# 05_ZYNQ_ETHERNET.net
KiCad netlist of a schematic drawn in Altium Designer
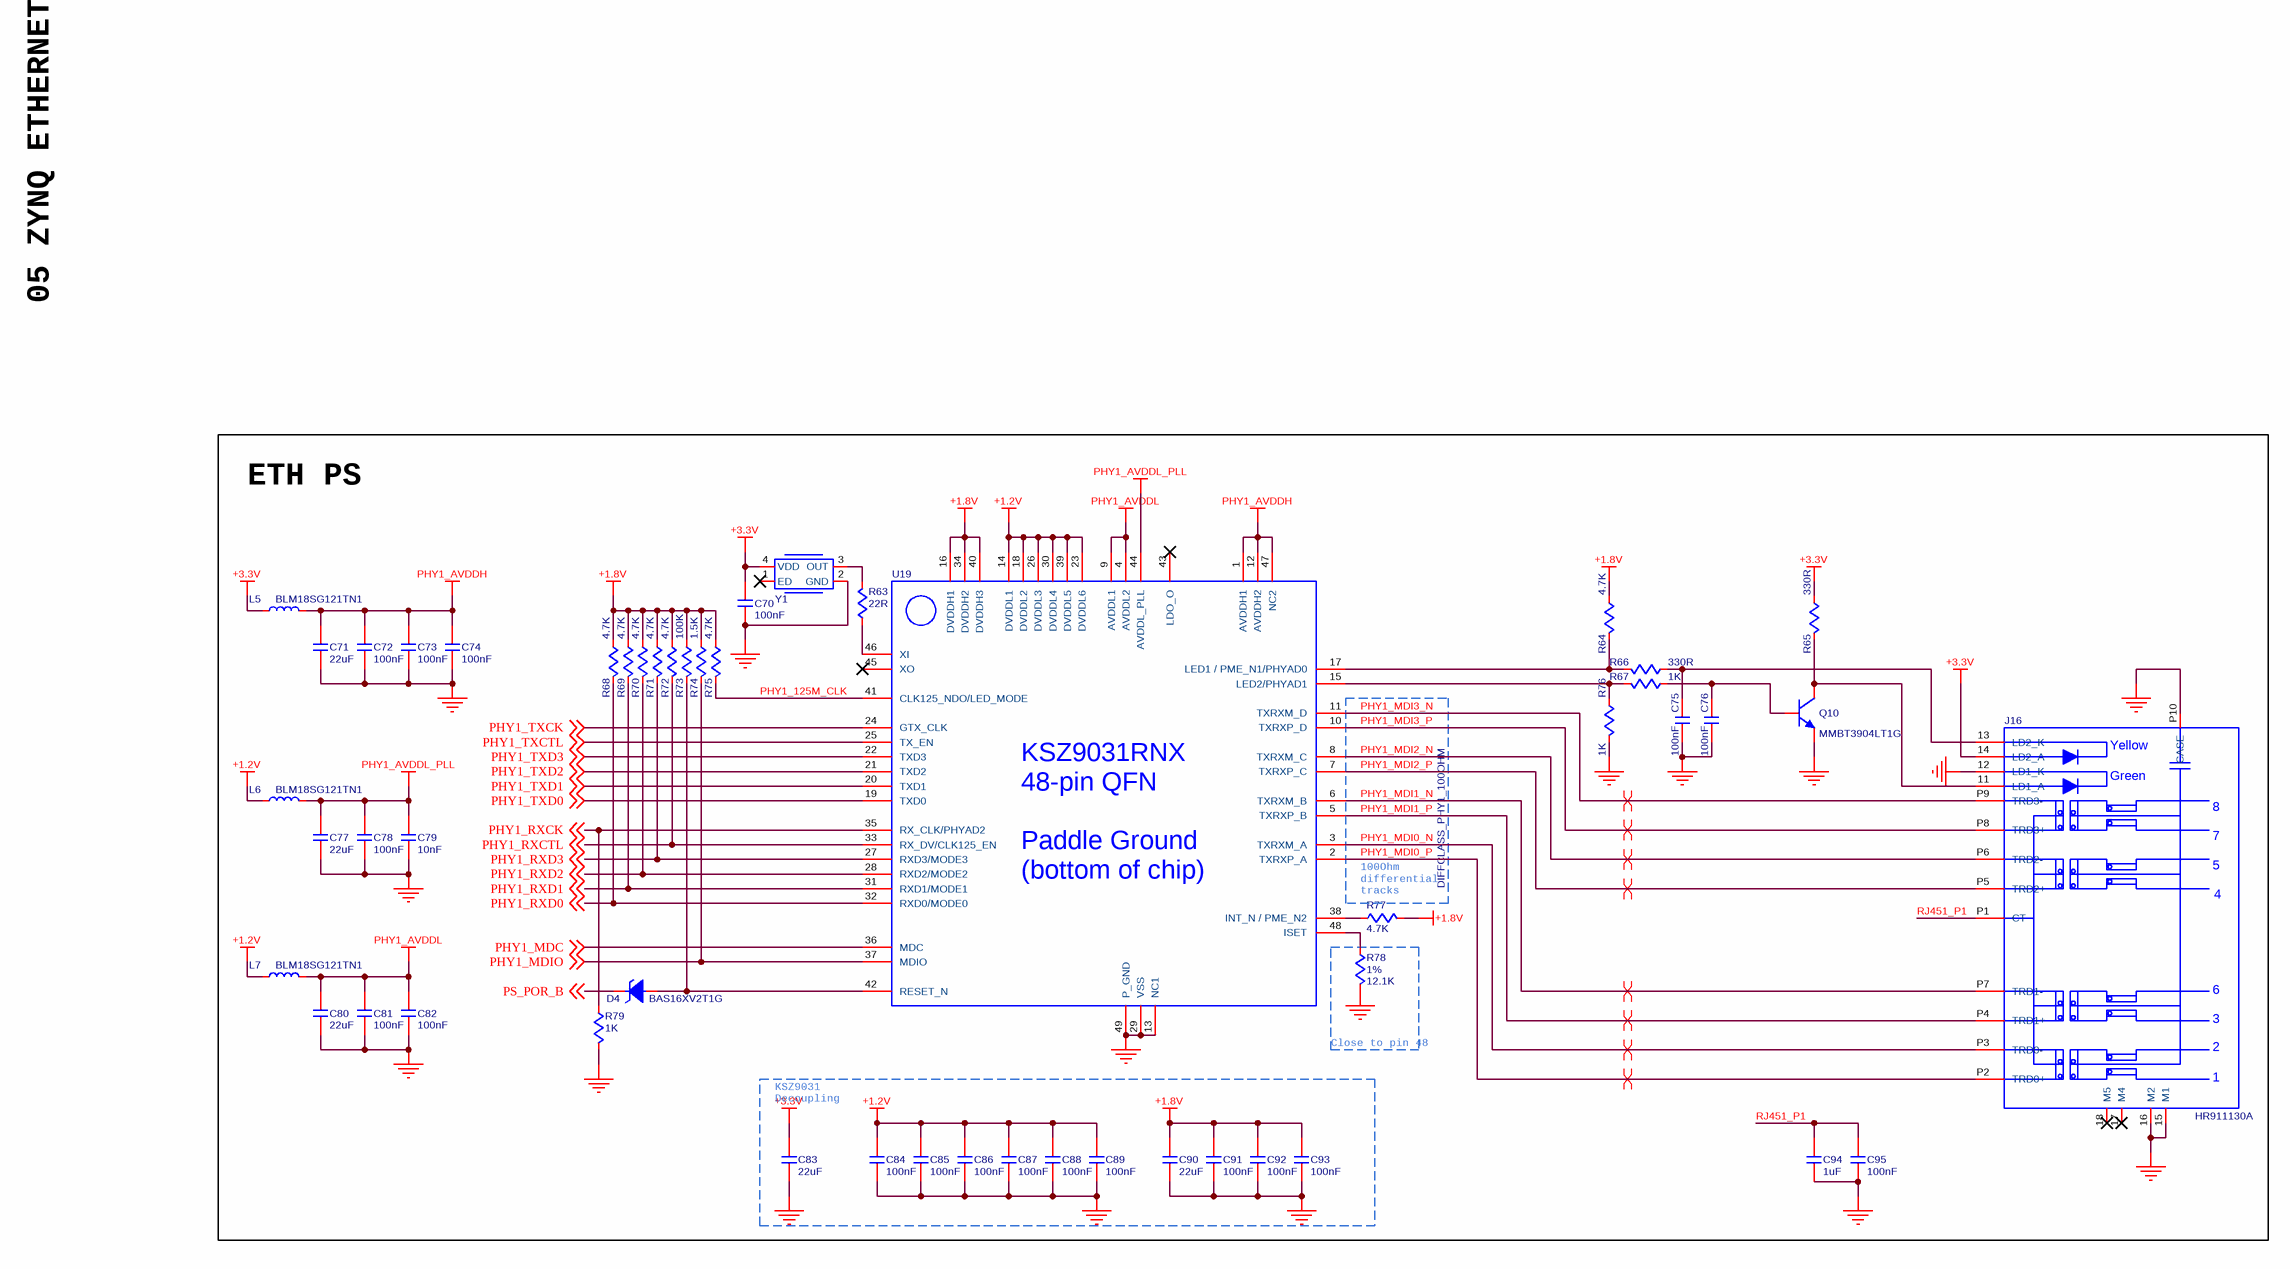
[diagram p0: 05_ZYNQ_ETHERNET.SchDoc]

(export (version "E")
  (design (tool "Eeschema 10.0.6"))
  (components
    (comp (ref "C70")
      (value "100nF")
      (footprint "zynq:C0402")
      (fields (field (name "VOLTAGE") "25V") (field (name "Comment") "C-NOMO"))
      (libsource (lib "zynq") (part "C-NOMO"))
    )
    (comp (ref "C71")
      (value "22uF")
      (footprint "zynq:C0805")
      (fields (field (name "VOLTAGE") "25V") (field (name "Comment") "C-NOMO"))
      (libsource (lib "zynq") (part "C-NOMO"))
    )
    (comp (ref "C72")
      (value "100nF")
      (footprint "zynq:C0402")
      (fields (field (name "VOLTAGE") "25V") (field (name "Comment") "C-NOMO"))
      (libsource (lib "zynq") (part "C-NOMO"))
    )
    (comp (ref "C73")
      (value "100nF")
      (footprint "zynq:C0402")
      (fields (field (name "VOLTAGE") "25V") (field (name "Comment") "C-NOMO"))
      (libsource (lib "zynq") (part "C-NOMO"))
    )
    (comp (ref "C74")
      (value "100nF")
      (footprint "zynq:C0402")
      (fields (field (name "VOLTAGE") "25V") (field (name "Comment") "C-NOMO"))
      (libsource (lib "zynq") (part "C-NOMO"))
    )
    (comp (ref "C75")
      (value "100nF")
      (footprint "zynq:C0402")
      (fields (field (name "VOLTAGE") "25V") (field (name "Comment") "C-NOMO"))
      (libsource (lib "zynq") (part "C-NOMO"))
    )
    (comp (ref "C76")
      (value "100nF")
      (footprint "zynq:C0402")
      (fields (field (name "VOLTAGE") "25V") (field (name "Comment") "C-NOMO"))
      (libsource (lib "zynq") (part "C-NOMO"))
    )
    (comp (ref "C77")
      (value "22uF")
      (footprint "zynq:C0805")
      (fields (field (name "VOLTAGE") "25V") (field (name "Comment") "C-NOMO"))
      (libsource (lib "zynq") (part "C-NOMO"))
    )
    (comp (ref "C78")
      (value "100nF")
      (footprint "zynq:C0402")
      (fields (field (name "VOLTAGE") "25V") (field (name "Comment") "C-NOMO"))
      (libsource (lib "zynq") (part "C-NOMO"))
    )
    (comp (ref "C79")
      (value "10nF")
      (footprint "zynq:C0402")
      (fields (field (name "VOLTAGE") "25V") (field (name "Comment") "C-NOMO"))
      (libsource (lib "zynq") (part "C-NOMO"))
    )
    (comp (ref "C80")
      (value "22uF")
      (footprint "zynq:C0805")
      (fields (field (name "VOLTAGE") "25V") (field (name "Comment") "C-NOMO"))
      (libsource (lib "zynq") (part "C-NOMO"))
    )
    (comp (ref "C81")
      (value "100nF")
      (footprint "zynq:C0402")
      (fields (field (name "VOLTAGE") "25V") (field (name "Comment") "C-NOMO"))
      (libsource (lib "zynq") (part "C-NOMO"))
    )
    (comp (ref "C82")
      (value "100nF")
      (footprint "zynq:C0402")
      (fields (field (name "VOLTAGE") "25V") (field (name "Comment") "C-NOMO"))
      (libsource (lib "zynq") (part "C-NOMO"))
    )
    (comp (ref "C83")
      (value "22uF")
      (footprint "zynq:C0805")
      (fields (field (name "VOLTAGE") "25V") (field (name "Comment") "C-NOMO"))
      (libsource (lib "zynq") (part "C-NOMO"))
    )
    (comp (ref "C84")
      (value "100nF")
      (footprint "zynq:C0402")
      (fields (field (name "VOLTAGE") "25V") (field (name "Comment") "C-NOMO"))
      (libsource (lib "zynq") (part "C-NOMO"))
    )
    (comp (ref "C85")
      (value "100nF")
      (footprint "zynq:C0402")
      (fields (field (name "VOLTAGE") "25V") (field (name "Comment") "C-NOMO"))
      (libsource (lib "zynq") (part "C-NOMO"))
    )
    (comp (ref "C86")
      (value "100nF")
      (footprint "zynq:C0402")
      (fields (field (name "VOLTAGE") "25V") (field (name "Comment") "C-NOMO"))
      (libsource (lib "zynq") (part "C-NOMO"))
    )
    (comp (ref "C87")
      (value "100nF")
      (footprint "zynq:C0402")
      (fields (field (name "VOLTAGE") "25V") (field (name "Comment") "C-NOMO"))
      (libsource (lib "zynq") (part "C-NOMO"))
    )
    (comp (ref "C88")
      (value "100nF")
      (footprint "zynq:C0402")
      (fields (field (name "VOLTAGE") "25V") (field (name "Comment") "C-NOMO"))
      (libsource (lib "zynq") (part "C-NOMO"))
    )
    (comp (ref "C89")
      (value "100nF")
      (footprint "zynq:C0402")
      (fields (field (name "VOLTAGE") "25V") (field (name "Comment") "C-NOMO"))
      (libsource (lib "zynq") (part "C-NOMO"))
    )
    (comp (ref "C90")
      (value "22uF")
      (footprint "zynq:C0805")
      (fields (field (name "VOLTAGE") "25V") (field (name "Comment") "C-NOMO"))
      (libsource (lib "zynq") (part "C-NOMO"))
    )
    (comp (ref "C91")
      (value "100nF")
      (footprint "zynq:C0402")
      (fields (field (name "VOLTAGE") "25V") (field (name "Comment") "C-NOMO"))
      (libsource (lib "zynq") (part "C-NOMO"))
    )
    (comp (ref "C92")
      (value "100nF")
      (footprint "zynq:C0402")
      (fields (field (name "VOLTAGE") "25V") (field (name "Comment") "C-NOMO"))
      (libsource (lib "zynq") (part "C-NOMO"))
    )
    (comp (ref "C93")
      (value "100nF")
      (footprint "zynq:C0402")
      (fields (field (name "VOLTAGE") "25V") (field (name "Comment") "C-NOMO"))
      (libsource (lib "zynq") (part "C-NOMO"))
    )
    (comp (ref "C94")
      (value "1uF")
      (footprint "zynq:C0402")
      (fields (field (name "VOLTAGE") "25V") (field (name "Comment") "C-NOMO"))
      (libsource (lib "zynq") (part "C-NOMO"))
    )
    (comp (ref "C95")
      (value "100nF")
      (footprint "zynq:C0402")
      (fields (field (name "VOLTAGE") "25V") (field (name "Comment") "C-NOMO"))
      (libsource (lib "zynq") (part "C-NOMO"))
    )
    (comp (ref "D4") (value "BAS16XV2T1G") (footprint "zynq:SOD-523") (libsource (lib "zynq") (part "DIOD2")))
    (comp (ref "J16")
      (value "HR911130A")
      (footprint "zynq:RJ45-GE")
      (libsource (lib "zynq") (part "RJ45-GE"))
    )
    (comp (ref "L5")
      (value "BLM18SG121TN1")
      (footprint "zynq:L0603")
      (fields (field (name "PUBLISHER") "Altium Limited"))
      (libsource (lib "zynq") (part "L"))
    )
    (comp (ref "L6")
      (value "BLM18SG121TN1")
      (footprint "zynq:L0603")
      (fields (field (name "PUBLISHER") "Altium Limited"))
      (libsource (lib "zynq") (part "L"))
    )
    (comp (ref "L7")
      (value "BLM18SG121TN1")
      (footprint "zynq:L0603")
      (fields (field (name "PUBLISHER") "Altium Limited"))
      (libsource (lib "zynq") (part "L"))
    )
    (comp (ref "Q10") (value "MMBT3904LT1G") (footprint "zynq:SOT-23") (libsource (lib "zynq") (part "NPN")))
    (comp (ref "R63")
      (value "22R")
      (footprint "zynq:R0402")
      (fields (field (name "Comment") "R"))
      (libsource (lib "zynq") (part "R"))
    )
    (comp (ref "R64")
      (value "4.7K")
      (footprint "zynq:R0402")
      (fields (field (name "Comment") "R"))
      (libsource (lib "zynq") (part "R"))
    )
    (comp (ref "R65")
      (value "330R")
      (footprint "zynq:R0402")
      (fields (field (name "Comment") "R"))
      (libsource (lib "zynq") (part "R"))
    )
    (comp (ref "R66")
      (value "330R")
      (footprint "zynq:R0402")
      (fields (field (name "Comment") "R"))
      (libsource (lib "zynq") (part "R"))
    )
    (comp (ref "R67")
      (value "1K")
      (footprint "zynq:R0402")
      (fields (field (name "Comment") "R"))
      (libsource (lib "zynq") (part "R"))
    )
    (comp (ref "R68")
      (value "4.7K")
      (footprint "zynq:R0402")
      (fields (field (name "Comment") "R"))
      (libsource (lib "zynq") (part "R"))
    )
    (comp (ref "R69")
      (value "4.7K")
      (footprint "zynq:R0402")
      (fields (field (name "Comment") "R"))
      (libsource (lib "zynq") (part "R"))
    )
    (comp (ref "R70")
      (value "4.7K")
      (footprint "zynq:R0402")
      (fields (field (name "Comment") "R"))
      (libsource (lib "zynq") (part "R"))
    )
    (comp (ref "R71")
      (value "4.7K")
      (footprint "zynq:R0402")
      (fields (field (name "Comment") "R"))
      (libsource (lib "zynq") (part "R"))
    )
    (comp (ref "R72")
      (value "4.7K")
      (footprint "zynq:R0402")
      (fields (field (name "Comment") "R"))
      (libsource (lib "zynq") (part "R"))
    )
    (comp (ref "R73")
      (value "100K")
      (footprint "zynq:R0402")
      (fields (field (name "Comment") "R"))
      (libsource (lib "zynq") (part "R"))
    )
    (comp (ref "R74")
      (value "1.5K")
      (footprint "zynq:R0402")
      (fields (field (name "Comment") "R"))
      (libsource (lib "zynq") (part "R"))
    )
    (comp (ref "R75")
      (value "4.7K")
      (footprint "zynq:R0402")
      (fields (field (name "Comment") "R"))
      (libsource (lib "zynq") (part "R"))
    )
    (comp (ref "R76")
      (value "1K")
      (footprint "zynq:R0402")
      (fields (field (name "Comment") "R"))
      (libsource (lib "zynq") (part "R"))
    )
    (comp (ref "R77")
      (value "4.7K")
      (footprint "zynq:R0402")
      (fields (field (name "Comment") "R"))
      (libsource (lib "zynq") (part "R"))
    )
    (comp (ref "R78")
      (value "12.1K")
      (footprint "zynq:R0402")
      (fields (field (name "PRECISION") "1%") (field (name "Comment") "R"))
      (libsource (lib "zynq") (part "R"))
    )
    (comp (ref "R79")
      (value "1K")
      (footprint "zynq:R0402")
      (fields (field (name "Comment") "R"))
      (libsource (lib "zynq") (part "R"))
    )
    (comp (ref "U19")
      (value "KSZ9031RNX")
      (footprint "zynq:KSZ9031")
      (libsource (lib "zynq") (part "KSZ9031RNX"))
    )
    (comp (ref "Y1") (value "XTAL") (footprint "zynq:OSC3225") (libsource (lib "zynq") (part "XTAL")))
  )
  (nets
    (net (code "1") (name "+1.2V") (class "Default")
      (node (ref "C84") (pin "2") (pinfunction "2_2") (pintype "passive"))
      (node (ref "C85") (pin "2") (pinfunction "2_2") (pintype "passive"))
      (node (ref "C86") (pin "2") (pinfunction "2_2") (pintype "passive"))
      (node (ref "C87") (pin "2") (pinfunction "2_2") (pintype "passive"))
      (node (ref "C88") (pin "2") (pinfunction "2_2") (pintype "passive"))
      (node (ref "C89") (pin "2") (pinfunction "2_2") (pintype "passive"))
      (node (ref "L6") (pin "1") (pinfunction "1_1") (pintype "passive"))
      (node (ref "L7") (pin "1") (pinfunction "1_1") (pintype "passive"))
      (node (ref "U19") (pin "14") (pinfunction "DVDDL1_14") (pintype "passive"))
      (node (ref "U19") (pin "18") (pinfunction "DVDDL2_18") (pintype "passive"))
      (node (ref "U19") (pin "23") (pinfunction "DVDDL6_23") (pintype "passive"))
      (node (ref "U19") (pin "26") (pinfunction "DVDDL3_26") (pintype "passive"))
      (node (ref "U19") (pin "30") (pinfunction "DVDDL4_30") (pintype "passive"))
      (node (ref "U19") (pin "39") (pinfunction "DVDDL5_39") (pintype "passive"))
    )
    (net (code "2") (name "+1.8V") (class "Default")
      (node (ref "C90") (pin "2") (pinfunction "2_2") (pintype "passive"))
      (node (ref "C91") (pin "2") (pinfunction "2_2") (pintype "passive"))
      (node (ref "C92") (pin "2") (pinfunction "2_2") (pintype "passive"))
      (node (ref "C93") (pin "2") (pinfunction "2_2") (pintype "passive"))
      (node (ref "R64") (pin "2") (pinfunction "2_2") (pintype "passive"))
      (node (ref "R68") (pin "2") (pinfunction "2_2") (pintype "passive"))
      (node (ref "R69") (pin "2") (pinfunction "2_2") (pintype "passive"))
      (node (ref "R70") (pin "2") (pinfunction "2_2") (pintype "passive"))
      (node (ref "R71") (pin "2") (pinfunction "2_2") (pintype "passive"))
      (node (ref "R72") (pin "2") (pinfunction "2_2") (pintype "passive"))
      (node (ref "R73") (pin "2") (pinfunction "2_2") (pintype "passive"))
      (node (ref "R74") (pin "2") (pinfunction "2_2") (pintype "passive"))
      (node (ref "R75") (pin "2") (pinfunction "2_2") (pintype "passive"))
      (node (ref "R77") (pin "1") (pinfunction "1_1") (pintype "passive"))
      (node (ref "U19") (pin "16") (pinfunction "DVDDH1_16") (pintype "passive"))
      (node (ref "U19") (pin "34") (pinfunction "DVDDH2_34") (pintype "passive"))
      (node (ref "U19") (pin "40") (pinfunction "DVDDH3_40") (pintype "passive"))
    )
    (net (code "3") (name "+3.3V") (class "Default")
      (node (ref "C70") (pin "2") (pinfunction "2_2") (pintype "passive"))
      (node (ref "C83") (pin "2") (pinfunction "2_2") (pintype "passive"))
      (node (ref "J16") (pin "14") (pinfunction "LD2_A_14") (pintype "passive"))
      (node (ref "L5") (pin "1") (pinfunction "1_1") (pintype "passive"))
      (node (ref "R65") (pin "2") (pinfunction "2_2") (pintype "passive"))
      (node (ref "Y1") (pin "4") (pinfunction "VDD_4") (pintype "passive"))
    )
    (net (code "4") (name "/PHY1_125M_CLK") (class "Default")
      (node (ref "R75") (pin "1") (pinfunction "1_1") (pintype "passive"))
      (node (ref "U19") (pin "41") (pinfunction "CLK125_NDO/LED_MODE_41") (pintype "passive"))
    )
    (net (code "5") (name "/PHY1_MDI0_N") (class "Default")
      (node (ref "J16") (pin "P3") (pinfunction "TRD0-_P3") (pintype "passive"))
      (node (ref "U19") (pin "3") (pinfunction "TXRXM_A_3") (pintype "passive"))
    )
    (net (code "6") (name "/PHY1_MDI0_P") (class "Default")
      (node (ref "J16") (pin "P2") (pinfunction "TRD0+_P2") (pintype "passive"))
      (node (ref "U19") (pin "2") (pinfunction "TXRXP_A_2") (pintype "passive"))
    )
    (net (code "7") (name "/PHY1_MDI1_N") (class "Default")
      (node (ref "J16") (pin "P7") (pinfunction "TRD1-_P7") (pintype "passive"))
      (node (ref "U19") (pin "6") (pinfunction "TXRXM_B_6") (pintype "passive"))
    )
    (net (code "8") (name "/PHY1_MDI1_P") (class "Default")
      (node (ref "J16") (pin "P4") (pinfunction "TRD1+_P4") (pintype "passive"))
      (node (ref "U19") (pin "5") (pinfunction "TXRXP_B_5") (pintype "passive"))
    )
    (net (code "9") (name "/PHY1_MDI2_N") (class "Default")
      (node (ref "J16") (pin "P6") (pinfunction "TRD2-_P6") (pintype "passive"))
      (node (ref "U19") (pin "8") (pinfunction "TXRXM_C_8") (pintype "passive"))
    )
    (net (code "10") (name "/PHY1_MDI2_P") (class "Default")
      (node (ref "J16") (pin "P5") (pinfunction "TRD2+_P5") (pintype "passive"))
      (node (ref "U19") (pin "7") (pinfunction "TXRXP_C_7") (pintype "passive"))
    )
    (net (code "11") (name "/PHY1_MDI3_N") (class "Default")
      (node (ref "J16") (pin "P9") (pinfunction "TRD3-_P9") (pintype "passive"))
      (node (ref "U19") (pin "11") (pinfunction "TXRXM_D_11") (pintype "passive"))
    )
    (net (code "12") (name "/PHY1_MDI3_P") (class "Default")
      (node (ref "J16") (pin "P8") (pinfunction "TRD3+_P8") (pintype "passive"))
      (node (ref "U19") (pin "10") (pinfunction "TXRXP_D_10") (pintype "passive"))
    )
    (net (code "13") (name "/RJ451_P1") (class "Default")
      (node (ref "C94") (pin "2") (pinfunction "2_2") (pintype "passive"))
      (node (ref "C95") (pin "2") (pinfunction "2_2") (pintype "passive"))
      (node (ref "J16") (pin "P1") (pinfunction "CT_P1") (pintype "passive"))
    )
    (net (code "14") (name "GND") (class "Default")
      (node (ref "C70") (pin "1") (pinfunction "1_1") (pintype "passive"))
      (node (ref "C71") (pin "1") (pinfunction "1_1") (pintype "passive"))
      (node (ref "C72") (pin "1") (pinfunction "1_1") (pintype "passive"))
      (node (ref "C73") (pin "1") (pinfunction "1_1") (pintype "passive"))
      (node (ref "C74") (pin "1") (pinfunction "1_1") (pintype "passive"))
      (node (ref "C75") (pin "1") (pinfunction "1_1") (pintype "passive"))
      (node (ref "C76") (pin "1") (pinfunction "1_1") (pintype "passive"))
      (node (ref "C77") (pin "1") (pinfunction "1_1") (pintype "passive"))
      (node (ref "C78") (pin "1") (pinfunction "1_1") (pintype "passive"))
      (node (ref "C79") (pin "1") (pinfunction "1_1") (pintype "passive"))
      (node (ref "C80") (pin "1") (pinfunction "1_1") (pintype "passive"))
      (node (ref "C81") (pin "1") (pinfunction "1_1") (pintype "passive"))
      (node (ref "C82") (pin "1") (pinfunction "1_1") (pintype "passive"))
      (node (ref "C83") (pin "1") (pinfunction "1_1") (pintype "passive"))
      (node (ref "C84") (pin "1") (pinfunction "1_1") (pintype "passive"))
      (node (ref "C85") (pin "1") (pinfunction "1_1") (pintype "passive"))
      (node (ref "C86") (pin "1") (pinfunction "1_1") (pintype "passive"))
      (node (ref "C87") (pin "1") (pinfunction "1_1") (pintype "passive"))
      (node (ref "C88") (pin "1") (pinfunction "1_1") (pintype "passive"))
      (node (ref "C89") (pin "1") (pinfunction "1_1") (pintype "passive"))
      (node (ref "C90") (pin "1") (pinfunction "1_1") (pintype "passive"))
      (node (ref "C91") (pin "1") (pinfunction "1_1") (pintype "passive"))
      (node (ref "C92") (pin "1") (pinfunction "1_1") (pintype "passive"))
      (node (ref "C93") (pin "1") (pinfunction "1_1") (pintype "passive"))
      (node (ref "C94") (pin "1") (pinfunction "1_1") (pintype "passive"))
      (node (ref "C95") (pin "1") (pinfunction "1_1") (pintype "passive"))
      (node (ref "J16") (pin "12") (pinfunction "LD1_K_12") (pintype "passive"))
      (node (ref "J16") (pin "15") (pinfunction "M1_15") (pintype "passive"))
      (node (ref "J16") (pin "16") (pinfunction "M2_16") (pintype "passive"))
      (node (ref "J16") (pin "P10") (pinfunction "CASE_P10") (pintype "passive"))
      (node (ref "Q10") (pin "2") (pinfunction "E_2") (pintype "passive"))
      (node (ref "R76") (pin "1") (pinfunction "1_1") (pintype "passive"))
      (node (ref "R78") (pin "1") (pinfunction "1_1") (pintype "passive"))
      (node (ref "R79") (pin "1") (pinfunction "1_1") (pintype "passive"))
      (node (ref "U19") (pin "13") (pinfunction "NC1_13") (pintype "passive"))
      (node (ref "U19") (pin "29") (pinfunction "VSS_29") (pintype "passive"))
      (node (ref "U19") (pin "49") (pinfunction "P_GND_49") (pintype "passive"))
      (node (ref "Y1") (pin "2") (pinfunction "GND_2") (pintype "passive"))
    )
    (net (code "15") (name "Net-(J16-LD1_A)") (class "Default")
      (node (ref "J16") (pin "11") (pinfunction "LD1_A_11") (pintype "passive"))
      (node (ref "Q10") (pin "3") (pinfunction "C_3") (pintype "passive"))
      (node (ref "R65") (pin "1") (pinfunction "1_1") (pintype "passive"))
    )
    (net (code "16") (name "Net-(J16-LD2_K)") (class "Default")
      (node (ref "C75") (pin "2") (pinfunction "2_2") (pintype "passive"))
      (node (ref "J16") (pin "13") (pinfunction "LD2_K_13") (pintype "passive"))
      (node (ref "R66") (pin "2") (pinfunction "2_2") (pintype "passive"))
    )
    (net (code "17") (name "Net-(Q10-B)") (class "Default")
      (node (ref "C76") (pin "2") (pinfunction "2_2") (pintype "passive"))
      (node (ref "Q10") (pin "1") (pinfunction "B_1") (pintype "passive"))
      (node (ref "R67") (pin "2") (pinfunction "2_2") (pintype "passive"))
    )
    (net (code "18") (name "Net-(U19-INT_N_{slash}_PME_N2)") (class "Default")
      (node (ref "R77") (pin "2") (pinfunction "2_2") (pintype "passive"))
      (node (ref "U19") (pin "38") (pinfunction "INT_N_/_PME_N2_38") (pintype "passive"))
    )
    (net (code "19") (name "Net-(U19-ISET)") (class "Default")
      (node (ref "R78") (pin "2") (pinfunction "2_2") (pintype "passive"))
      (node (ref "U19") (pin "48") (pinfunction "ISET_48") (pintype "passive"))
    )
    (net (code "20") (name "Net-(U19-LED1_{slash}_PME_N1{slash}PHYAD0)") (class "Default")
      (node (ref "R64") (pin "1") (pinfunction "1_1") (pintype "passive"))
      (node (ref "R66") (pin "1") (pinfunction "1_1") (pintype "passive"))
      (node (ref "U19") (pin "17") (pinfunction "LED1_/_PME_N1/PHYAD0_17") (pintype "passive"))
    )
    (net (code "21") (name "Net-(U19-LED2{slash}PHYAD1)") (class "Default")
      (node (ref "R67") (pin "1") (pinfunction "1_1") (pintype "passive"))
      (node (ref "R76") (pin "2") (pinfunction "2_2") (pintype "passive"))
      (node (ref "U19") (pin "15") (pinfunction "LED2/PHYAD1_15") (pintype "passive"))
    )
    (net (code "22") (name "Net-(U19-RESET_N)") (class "Default")
      (node (ref "D4") (pin "2") (pinfunction "2_2") (pintype "passive"))
      (node (ref "R73") (pin "1") (pinfunction "1_1") (pintype "passive"))
      (node (ref "U19") (pin "42") (pinfunction "RESET_N_42") (pintype "passive"))
    )
    (net (code "23") (name "Net-(U19-XI)") (class "Default")
      (node (ref "R63") (pin "2") (pinfunction "2_2") (pintype "passive"))
      (node (ref "U19") (pin "46") (pinfunction "XI_46") (pintype "passive"))
    )
    (net (code "24") (name "Net-(Y1-OUT)") (class "Default")
      (node (ref "R63") (pin "1") (pinfunction "1_1") (pintype "passive"))
      (node (ref "Y1") (pin "3") (pinfunction "OUT_3") (pintype "passive"))
    )
    (net (code "25") (name "PHY1_AVDDH") (class "Default")
      (node (ref "C71") (pin "2") (pinfunction "2_2") (pintype "passive"))
      (node (ref "C72") (pin "2") (pinfunction "2_2") (pintype "passive"))
      (node (ref "C73") (pin "2") (pinfunction "2_2") (pintype "passive"))
      (node (ref "C74") (pin "2") (pinfunction "2_2") (pintype "passive"))
      (node (ref "L5") (pin "2") (pinfunction "2_2") (pintype "passive"))
      (node (ref "U19") (pin "1") (pinfunction "AVDDH1_1") (pintype "passive"))
      (node (ref "U19") (pin "12") (pinfunction "AVDDH2_12") (pintype "passive"))
      (node (ref "U19") (pin "47") (pinfunction "NC2_47") (pintype "passive"))
    )
    (net (code "26") (name "PHY1_AVDDL") (class "Default")
      (node (ref "C80") (pin "2") (pinfunction "2_2") (pintype "passive"))
      (node (ref "C81") (pin "2") (pinfunction "2_2") (pintype "passive"))
      (node (ref "C82") (pin "2") (pinfunction "2_2") (pintype "passive"))
      (node (ref "L7") (pin "2") (pinfunction "2_2") (pintype "passive"))
      (node (ref "U19") (pin "4") (pinfunction "AVDDL2_4") (pintype "passive"))
      (node (ref "U19") (pin "9") (pinfunction "AVDDL1_9") (pintype "passive"))
    )
    (net (code "27") (name "PHY1_AVDDL_PLL") (class "Default")
      (node (ref "C77") (pin "2") (pinfunction "2_2") (pintype "passive"))
      (node (ref "C78") (pin "2") (pinfunction "2_2") (pintype "passive"))
      (node (ref "C79") (pin "2") (pinfunction "2_2") (pintype "passive"))
      (node (ref "L6") (pin "2") (pinfunction "2_2") (pintype "passive"))
      (node (ref "U19") (pin "44") (pinfunction "AVDDL_PLL_44") (pintype "passive"))
    )
    (net (code "28") (name "PHY1_MDC") (class "Default")
      (node (ref "U19") (pin "36") (pinfunction "MDC_36") (pintype "passive"))
    )
    (net (code "29") (name "PHY1_MDIO") (class "Default")
      (node (ref "R74") (pin "1") (pinfunction "1_1") (pintype "passive"))
      (node (ref "U19") (pin "37") (pinfunction "MDIO_37") (pintype "passive"))
    )
    (net (code "30") (name "PHY1_RXCK") (class "Default")
      (node (ref "R79") (pin "2") (pinfunction "2_2") (pintype "passive"))
      (node (ref "U19") (pin "35") (pinfunction "RX_CLK/PHYAD2_35") (pintype "passive"))
    )
    (net (code "31") (name "PHY1_RXCTL") (class "Default")
      (node (ref "R72") (pin "1") (pinfunction "1_1") (pintype "passive"))
      (node (ref "U19") (pin "33") (pinfunction "RX_DV/CLK125_EN_33") (pintype "passive"))
    )
    (net (code "32") (name "PHY1_RXD0") (class "Default")
      (node (ref "R68") (pin "1") (pinfunction "1_1") (pintype "passive"))
      (node (ref "U19") (pin "32") (pinfunction "RXD0/MODE0_32") (pintype "passive"))
    )
    (net (code "33") (name "PHY1_RXD1") (class "Default")
      (node (ref "R69") (pin "1") (pinfunction "1_1") (pintype "passive"))
      (node (ref "U19") (pin "31") (pinfunction "RXD1/MODE1_31") (pintype "passive"))
    )
    (net (code "34") (name "PHY1_RXD2") (class "Default")
      (node (ref "R70") (pin "1") (pinfunction "1_1") (pintype "passive"))
      (node (ref "U19") (pin "28") (pinfunction "RXD2/MODE2_28") (pintype "passive"))
    )
    (net (code "35") (name "PHY1_RXD3") (class "Default")
      (node (ref "R71") (pin "1") (pinfunction "1_1") (pintype "passive"))
      (node (ref "U19") (pin "27") (pinfunction "RXD3/MODE3_27") (pintype "passive"))
    )
    (net (code "36") (name "PHY1_TXCK") (class "Default")
      (node (ref "U19") (pin "24") (pinfunction "GTX_CLK_24") (pintype "passive"))
    )
    (net (code "37") (name "PHY1_TXCTL") (class "Default")
      (node (ref "U19") (pin "25") (pinfunction "TX_EN_25") (pintype "passive"))
    )
    (net (code "38") (name "PHY1_TXD0") (class "Default")
      (node (ref "U19") (pin "19") (pinfunction "TXD0_19") (pintype "passive"))
    )
    (net (code "39") (name "PHY1_TXD1") (class "Default")
      (node (ref "U19") (pin "20") (pinfunction "TXD1_20") (pintype "passive"))
    )
    (net (code "40") (name "PHY1_TXD2") (class "Default")
      (node (ref "U19") (pin "21") (pinfunction "TXD2_21") (pintype "passive"))
    )
    (net (code "41") (name "PHY1_TXD3") (class "Default")
      (node (ref "U19") (pin "22") (pinfunction "TXD3_22") (pintype "passive"))
    )
    (net (code "42") (name "PS_POR_B") (class "Default")
      (node (ref "D4") (pin "1") (pinfunction "1_1") (pintype "passive"))
    )
    (net (code "43") (name "unconnected-(J16-M4-Pad17)") (class "Default")
      (node (ref "J16") (pin "17") (pinfunction "M4_17") (pintype "passive+no_connect"))
    )
    (net (code "44") (name "unconnected-(J16-M5-Pad18)") (class "Default")
      (node (ref "J16") (pin "18") (pinfunction "M5_18") (pintype "passive+no_connect"))
    )
    (net (code "45") (name "unconnected-(U19-LDO_O-Pad43)") (class "Default")
      (node (ref "U19") (pin "43") (pinfunction "LDO_O_43") (pintype "passive+no_connect"))
    )
    (net (code "46") (name "unconnected-(U19-XO-Pad45)") (class "Default")
      (node (ref "U19") (pin "45") (pinfunction "XO_45") (pintype "passive+no_connect"))
    )
    (net (code "47") (name "unconnected-(Y1-ED-Pad1)") (class "Default")
      (node (ref "Y1") (pin "1") (pinfunction "ED_1") (pintype "passive+no_connect"))
    )
  )
)
